# LED.net
KiCad netlist of a schematic drawn in Altium Designer
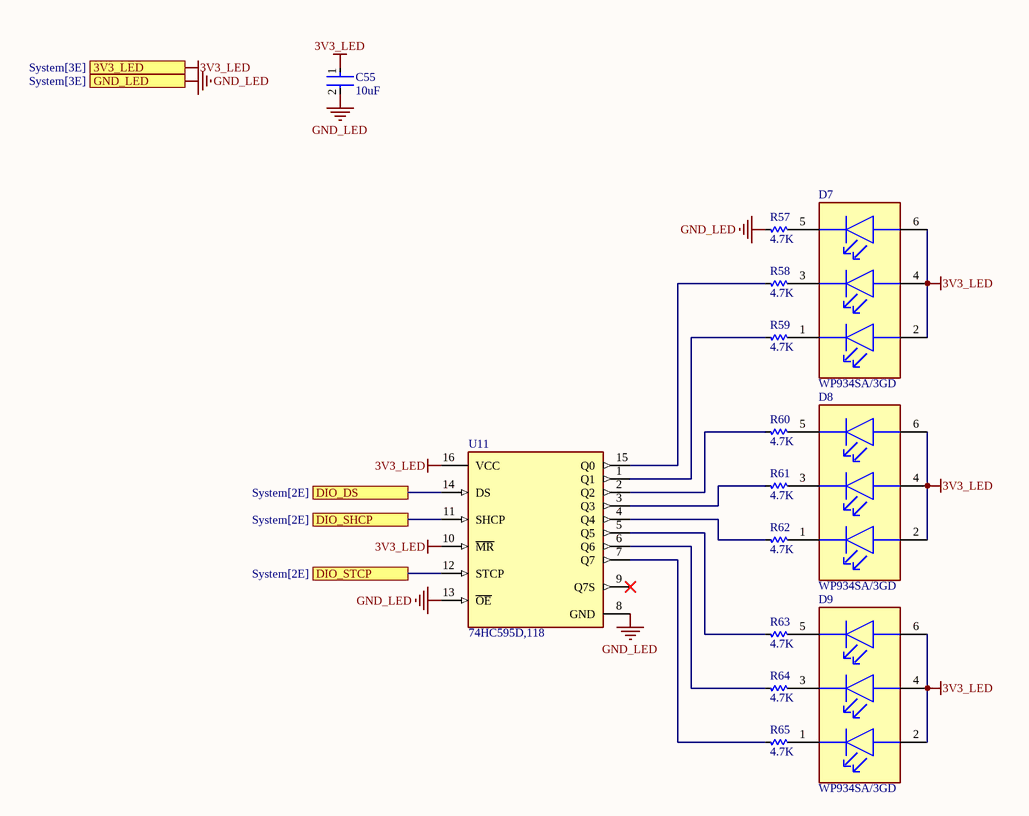
[diagram p0: LED.SchDoc]

(export (version "E")
  (design (tool "Eeschema 10.0.6"))
  (components
    (comp (ref "C55")
      (value "10uF")
      (footprint "FP-CC0603-DA-IPC_B")
      (description "CAP CER X7R 0603")
      (fields
        (field (name "OCTOPART") "https://octopart.com/cc0603krx7r7bb104-yageo-192941")
        (field (name "TOLERANCE") "0.1")
      )
      (libsource (lib "Altium Content Vault") (part "11868f565c42a9108669ba33697ecf6"))
    )
    (comp (ref "D7")
      (value "WP934SA/3GD")
      (footprint "FP-WP934SA-3GD-MFG")
      (description "LED IND 3MM TRI-LVL RA GRN DIFF")
      (libsource (lib "Altium Content Vault") (part "b98c470ba2667d6f0e0853aee89c694"))
    )
    (comp (ref "D8")
      (value "WP934SA/3GD")
      (footprint "FP-WP934SA-3GD-MFG")
      (description "LED IND 3MM TRI-LVL RA GRN DIFF")
      (libsource (lib "Altium Content Vault") (part "b98c470ba2667d6f0e0853aee89c694"))
    )
    (comp (ref "D9")
      (value "WP934SA/3GD")
      (footprint "FP-WP934SA-3GD-MFG")
      (description "LED IND 3MM TRI-LVL RA GRN DIFF")
      (libsource (lib "Altium Content Vault") (part "b98c470ba2667d6f0e0853aee89c694"))
    )
    (comp (ref "R57")
      (value "4.7K")
      (footprint "RES-SMD-0603")
      (description "Res 0603 5%")
      (fields
        (field (name "MANUFACTURER") "Generic Components")
        (field (name "PUBLISHER") "Altium Hobart Technology Centre")
      )
      (libsource (lib "TechMT.VN_Lib_Project v2") (part "Res-SMD"))
    )
    (comp (ref "R58")
      (value "4.7K")
      (footprint "RES-SMD-0603")
      (description "Res 0603 5%")
      (fields
        (field (name "MANUFACTURER") "Generic Components")
        (field (name "PUBLISHER") "Altium Hobart Technology Centre")
      )
      (libsource (lib "TechMT.VN_Lib_Project v2") (part "Res-SMD"))
    )
    (comp (ref "R59")
      (value "4.7K")
      (footprint "RES-SMD-0603")
      (description "Res 0603 5%")
      (fields
        (field (name "MANUFACTURER") "Generic Components")
        (field (name "PUBLISHER") "Altium Hobart Technology Centre")
      )
      (libsource (lib "TechMT.VN_Lib_Project v2") (part "Res-SMD"))
    )
    (comp (ref "R60")
      (value "4.7K")
      (footprint "RES-SMD-0603")
      (description "Res 0603 5%")
      (fields
        (field (name "MANUFACTURER") "Generic Components")
        (field (name "PUBLISHER") "Altium Hobart Technology Centre")
      )
      (libsource (lib "TechMT.VN_Lib_Project v2") (part "Res-SMD"))
    )
    (comp (ref "R61")
      (value "4.7K")
      (footprint "RES-SMD-0603")
      (description "Res 0603 5%")
      (fields
        (field (name "MANUFACTURER") "Generic Components")
        (field (name "PUBLISHER") "Altium Hobart Technology Centre")
      )
      (libsource (lib "TechMT.VN_Lib_Project v2") (part "Res-SMD"))
    )
    (comp (ref "R62")
      (value "4.7K")
      (footprint "RES-SMD-0603")
      (description "Res 0603 5%")
      (fields
        (field (name "MANUFACTURER") "Generic Components")
        (field (name "PUBLISHER") "Altium Hobart Technology Centre")
      )
      (libsource (lib "TechMT.VN_Lib_Project v2") (part "Res-SMD"))
    )
    (comp (ref "R63")
      (value "4.7K")
      (footprint "RES-SMD-0603")
      (description "Res 0603 5%")
      (fields
        (field (name "MANUFACTURER") "Generic Components")
        (field (name "PUBLISHER") "Altium Hobart Technology Centre")
      )
      (libsource (lib "TechMT.VN_Lib_Project v2") (part "Res-SMD"))
    )
    (comp (ref "R64")
      (value "4.7K")
      (footprint "RES-SMD-0603")
      (description "Res 0603 5%")
      (fields
        (field (name "MANUFACTURER") "Generic Components")
        (field (name "PUBLISHER") "Altium Hobart Technology Centre")
      )
      (libsource (lib "TechMT.VN_Lib_Project v2") (part "Res-SMD"))
    )
    (comp (ref "R65")
      (value "4.7K")
      (footprint "RES-SMD-0603")
      (description "Res 0603 5%")
      (fields
        (field (name "MANUFACTURER") "Generic Components")
        (field (name "PUBLISHER") "Altium Hobart Technology Centre")
      )
      (libsource (lib "TechMT.VN_Lib_Project v2") (part "Res-SMD"))
    )
    (comp (ref "U11")
      (value "74HC595D,118")
      (footprint "FP-SOT109-1-IPC_A")
      (description "IC SHIFT REGISTER 8BIT 16SOIC")
      (libsource (lib "Altium Content Vault") (part "7b153f231cfcc3ac06dee253bd56617"))
    )
  )
  (nets
    (net (code "1") (name "/DIO_DS") (class "Default")
      (node (ref "U11") (pin "14") (pinfunction "DS_14") (pintype "input"))
    )
    (net (code "2") (name "/DIO_SHCP") (class "Default")
      (node (ref "U11") (pin "11") (pinfunction "SHCP_11") (pintype "input"))
    )
    (net (code "3") (name "/DIO_STCP") (class "Default")
      (node (ref "U11") (pin "12") (pinfunction "STCP_12") (pintype "input"))
    )
    (net (code "4") (name "3V3_LED") (class "Default")
      (node (ref "C55") (pin "1") (pinfunction "1_1") (pintype "passive"))
      (node (ref "D7") (pin "2") (pinfunction "1_ANODE_2") (pintype "passive"))
      (node (ref "D7") (pin "4") (pinfunction "2_ANODE_4") (pintype "passive"))
      (node (ref "D7") (pin "6") (pinfunction "3_ANODE_6") (pintype "passive"))
      (node (ref "D8") (pin "2") (pinfunction "1_ANODE_2") (pintype "passive"))
      (node (ref "D8") (pin "4") (pinfunction "2_ANODE_4") (pintype "passive"))
      (node (ref "D8") (pin "6") (pinfunction "3_ANODE_6") (pintype "passive"))
      (node (ref "D9") (pin "2") (pinfunction "1_ANODE_2") (pintype "passive"))
      (node (ref "D9") (pin "4") (pinfunction "2_ANODE_4") (pintype "passive"))
      (node (ref "D9") (pin "6") (pinfunction "3_ANODE_6") (pintype "passive"))
      (node (ref "U11") (pin "10") (pinfunction "~{MR}_10") (pintype "input"))
      (node (ref "U11") (pin "16") (pinfunction "VCC_16") (pintype "power_in"))
    )
    (net (code "5") (name "GND_LED") (class "Default")
      (node (ref "C55") (pin "2") (pinfunction "2_2") (pintype "passive"))
      (node (ref "R57") (pin "2") (pinfunction "2_2") (pintype "passive"))
      (node (ref "U11") (pin "13") (pinfunction "~{OE}_13") (pintype "input"))
      (node (ref "U11") (pin "8") (pinfunction "GND_8") (pintype "power_in"))
    )
    (net (code "6") (name "Net-(D7-1_CATHODE)") (class "Default")
      (node (ref "D7") (pin "1") (pinfunction "1_CATHODE_1") (pintype "passive"))
      (node (ref "R59") (pin "1") (pinfunction "1_1") (pintype "passive"))
    )
    (net (code "7") (name "Net-(D7-2_CATHODE)") (class "Default")
      (node (ref "D7") (pin "3") (pinfunction "2_CATHODE_3") (pintype "passive"))
      (node (ref "R58") (pin "1") (pinfunction "1_1") (pintype "passive"))
    )
    (net (code "8") (name "Net-(D7-3_CATHODE)") (class "Default")
      (node (ref "D7") (pin "5") (pinfunction "3_CATHODE_5") (pintype "passive"))
      (node (ref "R57") (pin "1") (pinfunction "1_1") (pintype "passive"))
    )
    (net (code "9") (name "Net-(D8-1_CATHODE)") (class "Default")
      (node (ref "D8") (pin "1") (pinfunction "1_CATHODE_1") (pintype "passive"))
      (node (ref "R62") (pin "1") (pinfunction "1_1") (pintype "passive"))
    )
    (net (code "10") (name "Net-(D8-2_CATHODE)") (class "Default")
      (node (ref "D8") (pin "3") (pinfunction "2_CATHODE_3") (pintype "passive"))
      (node (ref "R61") (pin "1") (pinfunction "1_1") (pintype "passive"))
    )
    (net (code "11") (name "Net-(D8-3_CATHODE)") (class "Default")
      (node (ref "D8") (pin "5") (pinfunction "3_CATHODE_5") (pintype "passive"))
      (node (ref "R60") (pin "1") (pinfunction "1_1") (pintype "passive"))
    )
    (net (code "12") (name "Net-(D9-1_CATHODE)") (class "Default")
      (node (ref "D9") (pin "1") (pinfunction "1_CATHODE_1") (pintype "passive"))
      (node (ref "R65") (pin "1") (pinfunction "1_1") (pintype "passive"))
    )
    (net (code "13") (name "Net-(D9-2_CATHODE)") (class "Default")
      (node (ref "D9") (pin "3") (pinfunction "2_CATHODE_3") (pintype "passive"))
      (node (ref "R64") (pin "1") (pinfunction "1_1") (pintype "passive"))
    )
    (net (code "14") (name "Net-(D9-3_CATHODE)") (class "Default")
      (node (ref "D9") (pin "5") (pinfunction "3_CATHODE_5") (pintype "passive"))
      (node (ref "R63") (pin "1") (pinfunction "1_1") (pintype "passive"))
    )
    (net (code "15") (name "Net-(U11-Q0)") (class "Default")
      (node (ref "R58") (pin "2") (pinfunction "2_2") (pintype "passive"))
      (node (ref "U11") (pin "15") (pinfunction "Q0_15") (pintype "output"))
    )
    (net (code "16") (name "Net-(U11-Q1)") (class "Default")
      (node (ref "R59") (pin "2") (pinfunction "2_2") (pintype "passive"))
      (node (ref "U11") (pin "1") (pinfunction "Q1_1") (pintype "output"))
    )
    (net (code "17") (name "Net-(U11-Q2)") (class "Default")
      (node (ref "R60") (pin "2") (pinfunction "2_2") (pintype "passive"))
      (node (ref "U11") (pin "2") (pinfunction "Q2_2") (pintype "output"))
    )
    (net (code "18") (name "Net-(U11-Q3)") (class "Default")
      (node (ref "R61") (pin "2") (pinfunction "2_2") (pintype "passive"))
      (node (ref "U11") (pin "3") (pinfunction "Q3_3") (pintype "output"))
    )
    (net (code "19") (name "Net-(U11-Q4)") (class "Default")
      (node (ref "R62") (pin "2") (pinfunction "2_2") (pintype "passive"))
      (node (ref "U11") (pin "4") (pinfunction "Q4_4") (pintype "output"))
    )
    (net (code "20") (name "Net-(U11-Q5)") (class "Default")
      (node (ref "R63") (pin "2") (pinfunction "2_2") (pintype "passive"))
      (node (ref "U11") (pin "5") (pinfunction "Q5_5") (pintype "output"))
    )
    (net (code "21") (name "Net-(U11-Q6)") (class "Default")
      (node (ref "R64") (pin "2") (pinfunction "2_2") (pintype "passive"))
      (node (ref "U11") (pin "6") (pinfunction "Q6_6") (pintype "output"))
    )
    (net (code "22") (name "Net-(U11-Q7)") (class "Default")
      (node (ref "R65") (pin "2") (pinfunction "2_2") (pintype "passive"))
      (node (ref "U11") (pin "7") (pinfunction "Q7_7") (pintype "output"))
    )
    (net (code "23") (name "unconnected-(U11-Q7S-Pad9)") (class "Default")
      (node (ref "U11") (pin "9") (pinfunction "Q7S_9") (pintype "output+no_connect"))
    )
  )
)
